# H03.net
KiCad netlist of a schematic drawn in EAGLE
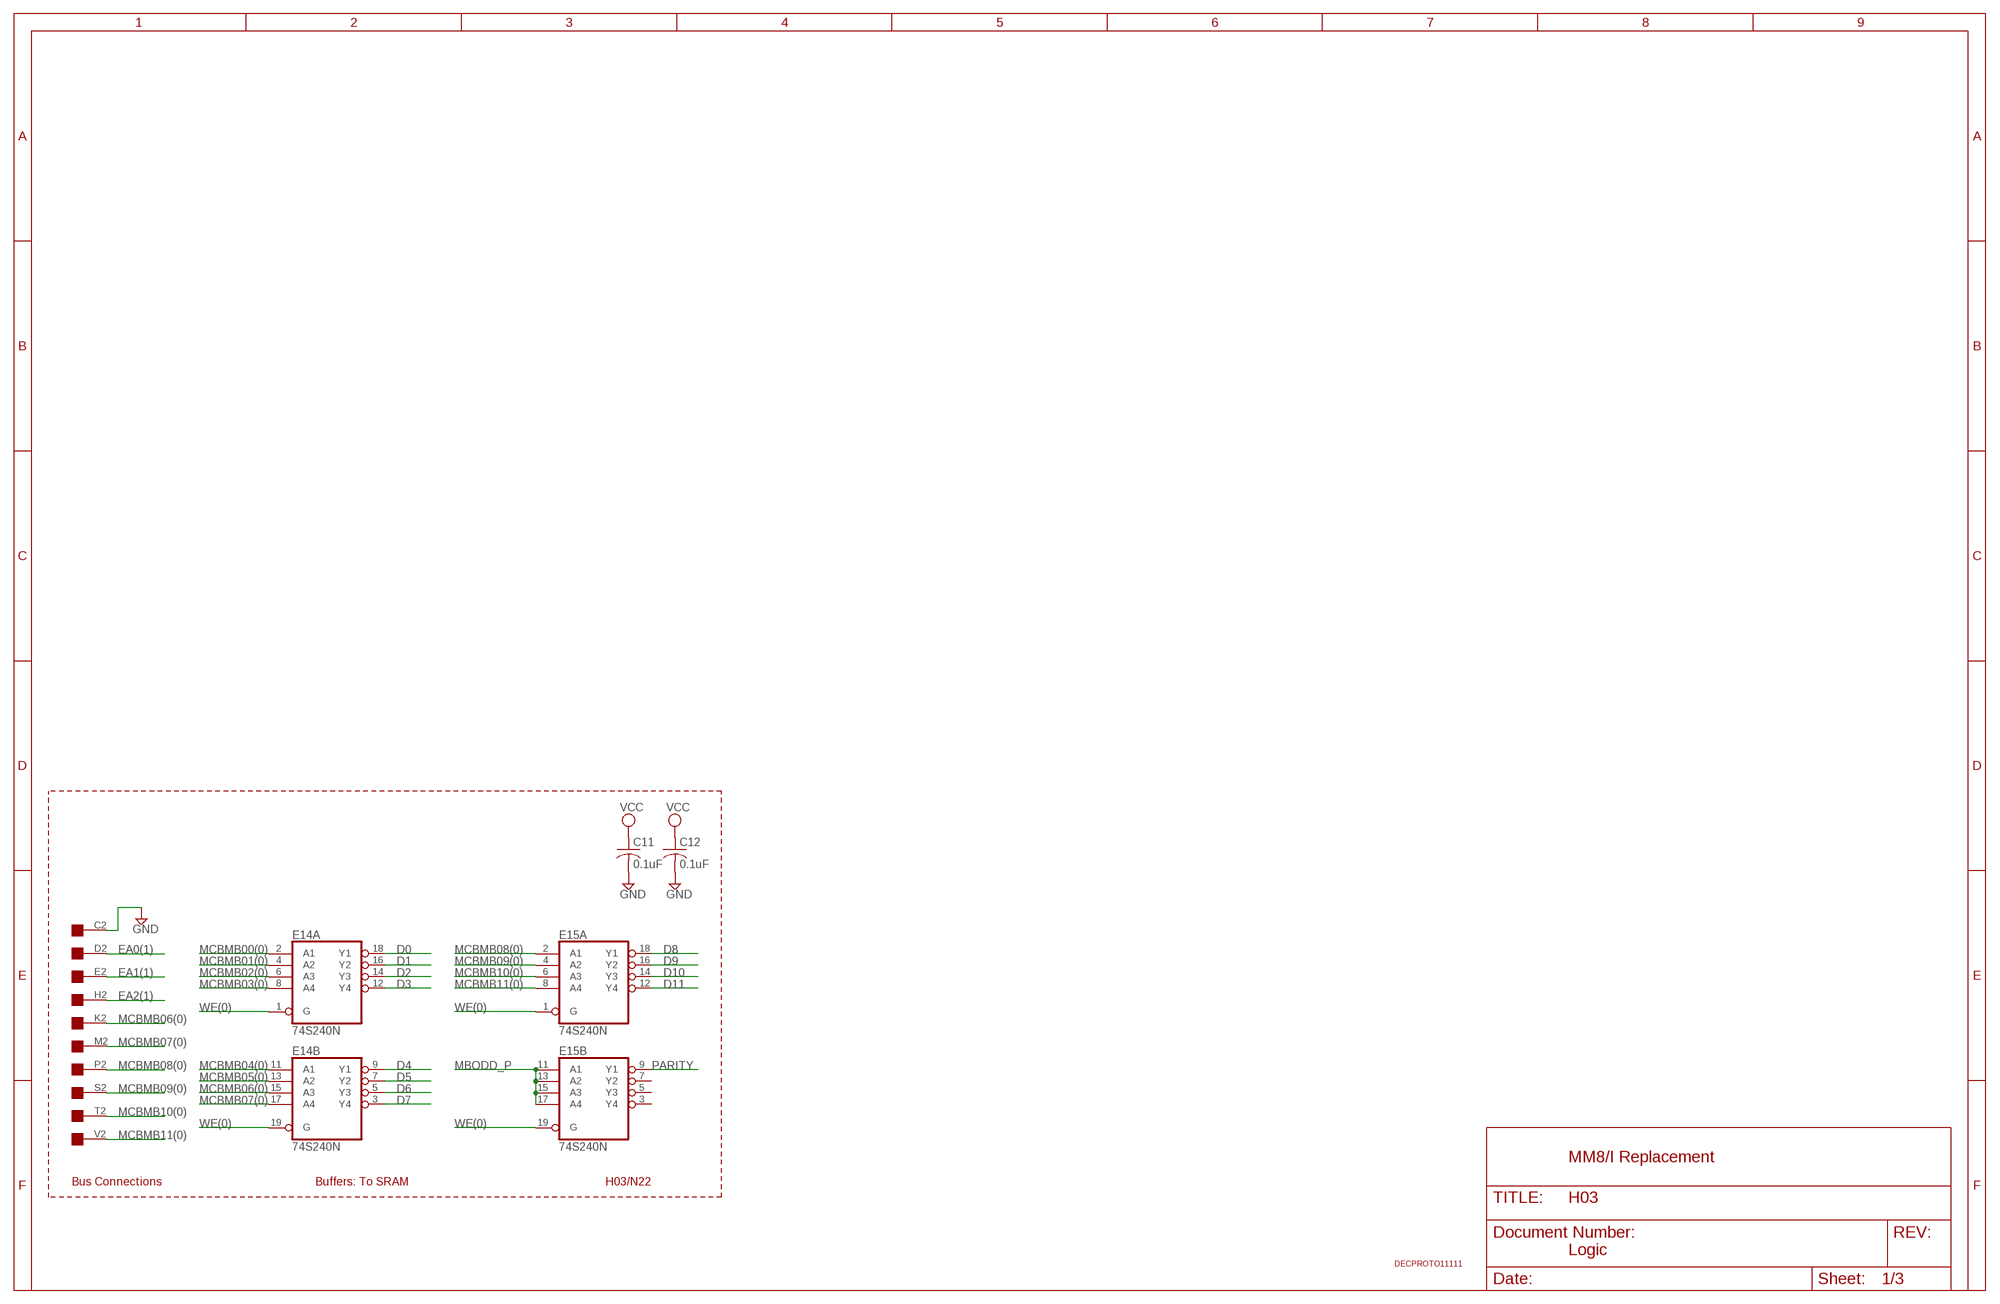
[diagram p0: schematic, sheet 1]
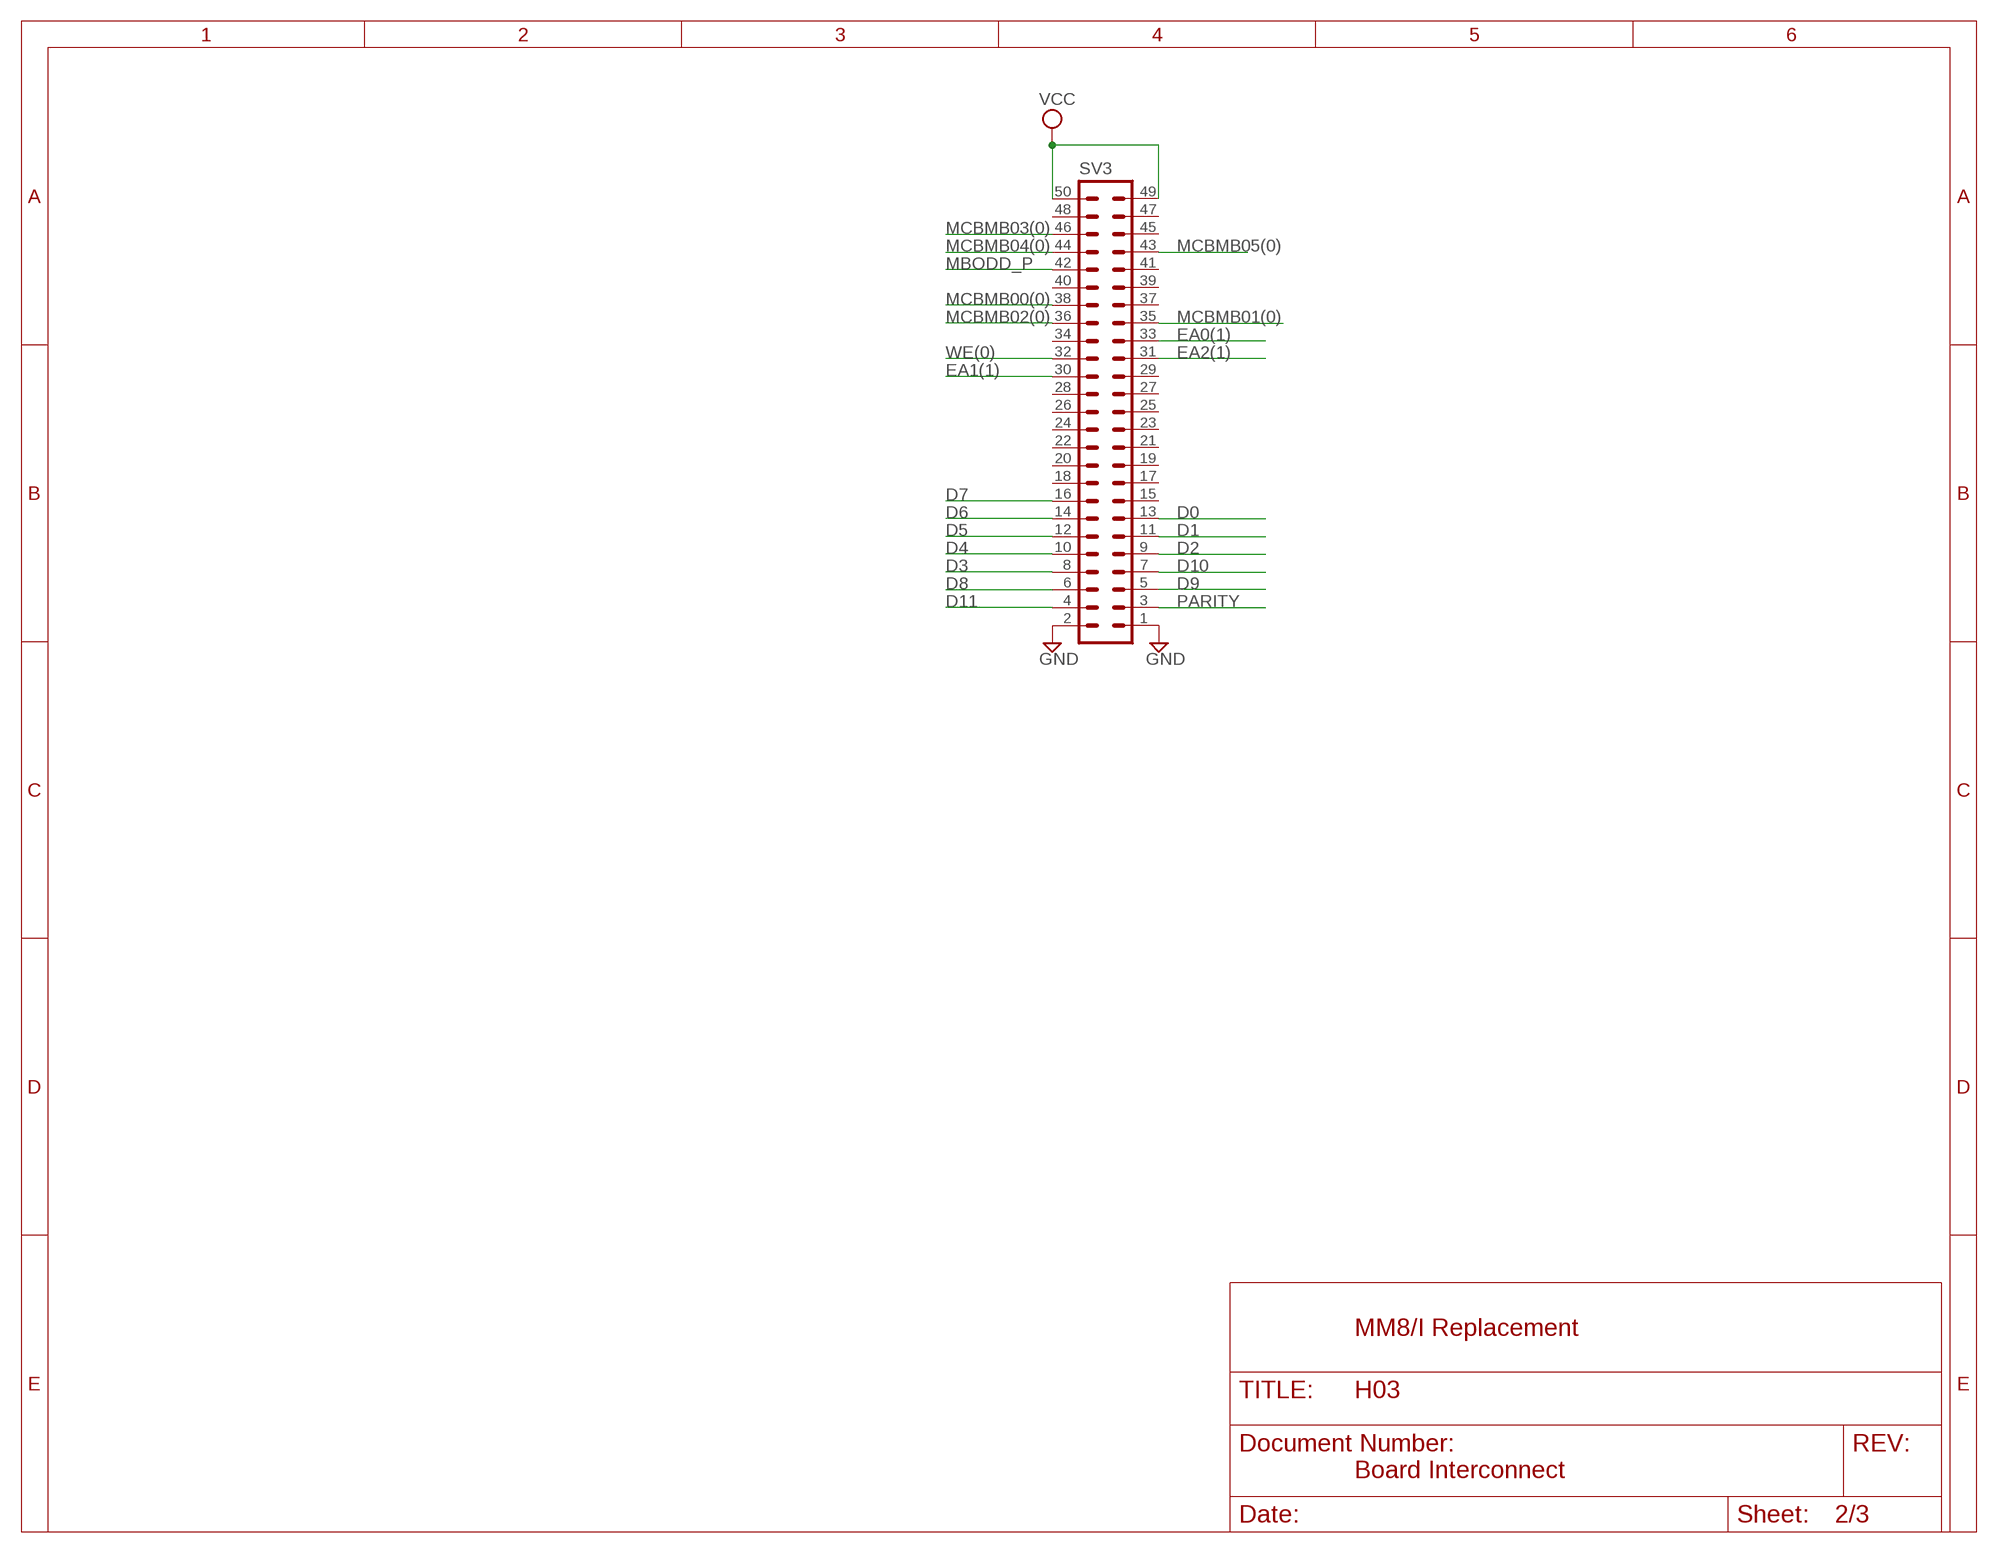
[diagram p1: schematic, sheet 2]
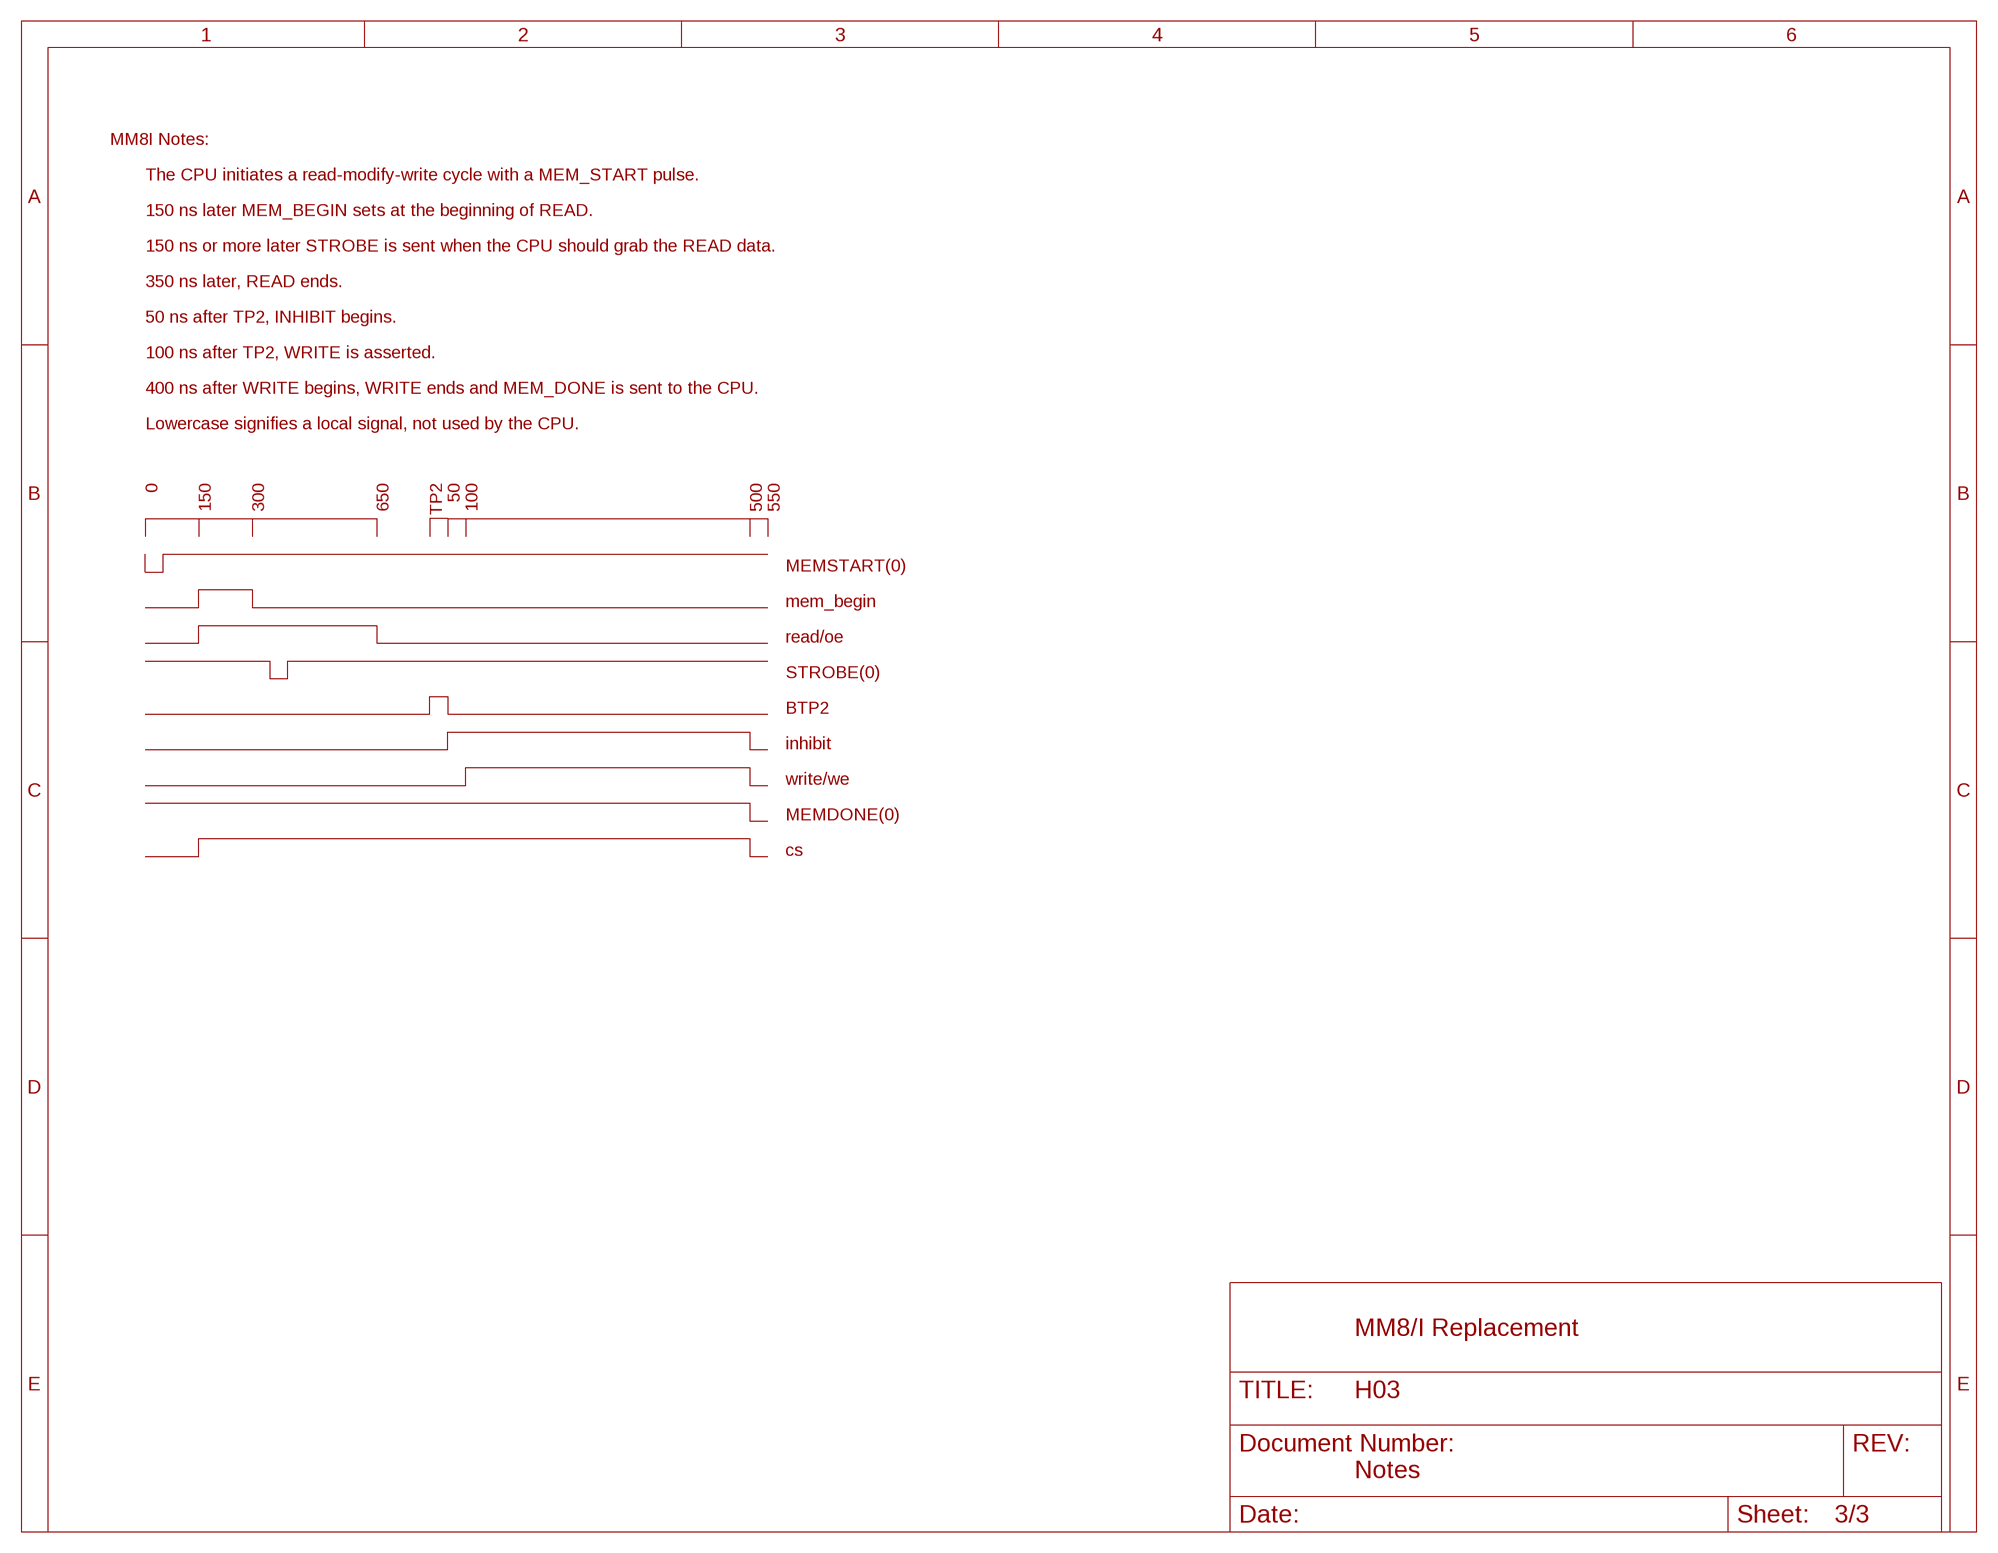
[diagram p2: schematic, sheet 3]

(export (version "E")
  (design (tool "Eeschema 10.0.6"))
  (components
    (comp (ref "C11")
      (value "0.1uF")
      (footprint "eagle-import:C050-025X075")
      (libsource (lib "eagle-import") (part "C-US050-025X075"))
    )
    (comp (ref "C12")
      (value "0.1uF")
      (footprint "eagle-import:C050-025X075")
      (libsource (lib "eagle-import") (part "C-US050-025X075"))
    )
    (comp (ref "E14")
      (value "74S240N")
      (footprint "eagle-import:DIL20")
      (libsource (lib "eagle-import") (part "74240NS"))
    )
    (comp (ref "E15")
      (value "74S240N")
      (footprint "eagle-import:DIL20")
      (libsource (lib "eagle-import") (part "74240NS"))
    )
    (comp (ref "H03")
      (value "EDGE-1")
      (footprint "eagle-import:EDGE-CON1")
      (libsource (lib "eagle-import") (part "EDGE-1"))
    )
    (comp (ref "U$6")
      (value "DECPROTO11111")
      (footprint "eagle-import:DECPROTO11111")
      (libsource (lib "eagle-import") (part "DECPROTO11111"))
    )
    (comp (ref "SV3")
      (value "ML50L")
      (footprint "eagle-import:ML50L")
      (libsource (lib "eagle-import") (part "ML50L"))
    )
  )
  (nets
    (net (code "1") (name "D0") (class "Default")
      (node (ref "E14") (pin "18") (pinfunction "Y1_18") (pintype "tri_state"))
      (node (ref "SV3") (pin "13") (pinfunction "13_13") (pintype "passive"))
    )
    (net (code "2") (name "D1") (class "Default")
      (node (ref "E14") (pin "16") (pinfunction "Y2_16") (pintype "tri_state"))
      (node (ref "SV3") (pin "11") (pinfunction "11_11") (pintype "passive"))
    )
    (net (code "3") (name "D2") (class "Default")
      (node (ref "E14") (pin "14") (pinfunction "Y3_14") (pintype "tri_state"))
      (node (ref "SV3") (pin "9") (pinfunction "9_9") (pintype "passive"))
    )
    (net (code "4") (name "D3") (class "Default")
      (node (ref "E14") (pin "12") (pinfunction "Y4_12") (pintype "tri_state"))
      (node (ref "SV3") (pin "8") (pinfunction "8_8") (pintype "passive"))
    )
    (net (code "5") (name "D4") (class "Default")
      (node (ref "E14") (pin "9") (pinfunction "Y1_9") (pintype "tri_state"))
      (node (ref "SV3") (pin "10") (pinfunction "10_10") (pintype "passive"))
    )
    (net (code "6") (name "D5") (class "Default")
      (node (ref "E14") (pin "7") (pinfunction "Y2_7") (pintype "tri_state"))
      (node (ref "SV3") (pin "12") (pinfunction "12_12") (pintype "passive"))
    )
    (net (code "7") (name "D6") (class "Default")
      (node (ref "E14") (pin "5") (pinfunction "Y3_5") (pintype "tri_state"))
      (node (ref "SV3") (pin "14") (pinfunction "14_14") (pintype "passive"))
    )
    (net (code "8") (name "D7") (class "Default")
      (node (ref "E14") (pin "3") (pinfunction "Y4_3") (pintype "tri_state"))
      (node (ref "SV3") (pin "16") (pinfunction "16_16") (pintype "passive"))
    )
    (net (code "9") (name "D8") (class "Default")
      (node (ref "E15") (pin "18") (pinfunction "Y1_18") (pintype "tri_state"))
      (node (ref "SV3") (pin "6") (pinfunction "6_6") (pintype "passive"))
    )
    (net (code "10") (name "D9") (class "Default")
      (node (ref "E15") (pin "16") (pinfunction "Y2_16") (pintype "tri_state"))
      (node (ref "SV3") (pin "5") (pinfunction "5_5") (pintype "passive"))
    )
    (net (code "11") (name "D10") (class "Default")
      (node (ref "E15") (pin "14") (pinfunction "Y3_14") (pintype "tri_state"))
      (node (ref "SV3") (pin "7") (pinfunction "7_7") (pintype "passive"))
    )
    (net (code "12") (name "D11") (class "Default")
      (node (ref "E15") (pin "12") (pinfunction "Y4_12") (pintype "tri_state"))
      (node (ref "SV3") (pin "4") (pinfunction "4_4") (pintype "passive"))
    )
    (net (code "13") (name "EA0(1)") (class "Default")
      (node (ref "H03") (pin "D2") (pinfunction "1_D2") (pintype "bidirectional"))
      (node (ref "SV3") (pin "33") (pinfunction "33_33") (pintype "passive"))
    )
    (net (code "14") (name "EA1(1)") (class "Default")
      (node (ref "H03") (pin "E2") (pinfunction "1_E2") (pintype "bidirectional"))
      (node (ref "SV3") (pin "30") (pinfunction "30_30") (pintype "passive"))
    )
    (net (code "15") (name "EA2(1)") (class "Default")
      (node (ref "H03") (pin "H2") (pinfunction "1_H2") (pintype "bidirectional"))
      (node (ref "SV3") (pin "31") (pinfunction "31_31") (pintype "passive"))
    )
    (net (code "16") (name "GND") (class "Default")
      (node (ref "C11") (pin "2") (pinfunction "2_2") (pintype "passive"))
      (node (ref "C12") (pin "2") (pinfunction "2_2") (pintype "passive"))
      (node (ref "H03") (pin "C2") (pinfunction "1_C2") (pintype "bidirectional"))
      (node (ref "SV3") (pin "1") (pinfunction "1_1") (pintype "passive"))
      (node (ref "SV3") (pin "2") (pinfunction "2_2") (pintype "passive"))
    )
    (net (code "17") (name "MBODD_P") (class "Default")
      (node (ref "E15") (pin "11") (pinfunction "A1_11") (pintype "input"))
      (node (ref "E15") (pin "13") (pinfunction "A2_13") (pintype "input"))
      (node (ref "E15") (pin "15") (pinfunction "A3_15") (pintype "input"))
      (node (ref "E15") (pin "17") (pinfunction "A4_17") (pintype "input"))
      (node (ref "SV3") (pin "42") (pinfunction "42_42") (pintype "passive"))
    )
    (net (code "18") (name "MCBMB00(0)") (class "Default")
      (node (ref "E14") (pin "2") (pinfunction "A1_2") (pintype "input"))
      (node (ref "SV3") (pin "38") (pinfunction "38_38") (pintype "passive"))
    )
    (net (code "19") (name "MCBMB01(0)") (class "Default")
      (node (ref "E14") (pin "4") (pinfunction "A2_4") (pintype "input"))
      (node (ref "SV3") (pin "35") (pinfunction "35_35") (pintype "passive"))
    )
    (net (code "20") (name "MCBMB02(0)") (class "Default")
      (node (ref "E14") (pin "6") (pinfunction "A3_6") (pintype "input"))
      (node (ref "SV3") (pin "36") (pinfunction "36_36") (pintype "passive"))
    )
    (net (code "21") (name "MCBMB03(0)") (class "Default")
      (node (ref "E14") (pin "8") (pinfunction "A4_8") (pintype "input"))
      (node (ref "SV3") (pin "46") (pinfunction "46_46") (pintype "passive"))
    )
    (net (code "22") (name "MCBMB04(0)") (class "Default")
      (node (ref "E14") (pin "11") (pinfunction "A1_11") (pintype "input"))
      (node (ref "SV3") (pin "44") (pinfunction "44_44") (pintype "passive"))
    )
    (net (code "23") (name "MCBMB05(0)") (class "Default")
      (node (ref "E14") (pin "13") (pinfunction "A2_13") (pintype "input"))
      (node (ref "SV3") (pin "43") (pinfunction "43_43") (pintype "passive"))
    )
    (net (code "24") (name "MCBMB06(0)") (class "Default")
      (node (ref "E14") (pin "15") (pinfunction "A3_15") (pintype "input"))
      (node (ref "H03") (pin "K2") (pinfunction "1_K2") (pintype "bidirectional"))
    )
    (net (code "25") (name "MCBMB07(0)") (class "Default")
      (node (ref "E14") (pin "17") (pinfunction "A4_17") (pintype "input"))
      (node (ref "H03") (pin "M2") (pinfunction "1_M2") (pintype "bidirectional"))
    )
    (net (code "26") (name "MCBMB08(0)") (class "Default")
      (node (ref "E15") (pin "2") (pinfunction "A1_2") (pintype "input"))
      (node (ref "H03") (pin "P2") (pinfunction "1_P2") (pintype "bidirectional"))
    )
    (net (code "27") (name "MCBMB09(0)") (class "Default")
      (node (ref "E15") (pin "4") (pinfunction "A2_4") (pintype "input"))
      (node (ref "H03") (pin "S2") (pinfunction "1_S2") (pintype "bidirectional"))
    )
    (net (code "28") (name "MCBMB10(0)") (class "Default")
      (node (ref "E15") (pin "6") (pinfunction "A3_6") (pintype "input"))
      (node (ref "H03") (pin "T2") (pinfunction "1_T2") (pintype "bidirectional"))
    )
    (net (code "29") (name "MCBMB11(0)") (class "Default")
      (node (ref "E15") (pin "8") (pinfunction "A4_8") (pintype "input"))
      (node (ref "H03") (pin "V2") (pinfunction "1_V2") (pintype "bidirectional"))
    )
    (net (code "30") (name "PARITY") (class "Default")
      (node (ref "E15") (pin "9") (pinfunction "Y1_9") (pintype "tri_state"))
      (node (ref "SV3") (pin "3") (pinfunction "3_3") (pintype "passive"))
    )
    (net (code "31") (name "VCC") (class "Default")
      (node (ref "C11") (pin "1") (pinfunction "1_1") (pintype "passive"))
      (node (ref "C12") (pin "1") (pinfunction "1_1") (pintype "passive"))
      (node (ref "SV3") (pin "49") (pinfunction "49_49") (pintype "passive"))
      (node (ref "SV3") (pin "50") (pinfunction "50_50") (pintype "passive"))
    )
    (net (code "32") (name "WE(0)") (class "Default")
      (node (ref "E14") (pin "1") (pinfunction "G_1") (pintype "input"))
      (node (ref "E14") (pin "19") (pinfunction "G_19") (pintype "input"))
      (node (ref "E15") (pin "1") (pinfunction "G_1") (pintype "input"))
      (node (ref "E15") (pin "19") (pinfunction "G_19") (pintype "input"))
      (node (ref "SV3") (pin "32") (pinfunction "32_32") (pintype "passive"))
    )
    (net (code "33") (name "unconnected-(E15B-Y2-Pad7)") (class "Default")
      (node (ref "E15") (pin "7") (pinfunction "Y2_7") (pintype "tri_state"))
    )
    (net (code "34") (name "unconnected-(E15B-Y3-Pad5)") (class "Default")
      (node (ref "E15") (pin "5") (pinfunction "Y3_5") (pintype "tri_state"))
    )
    (net (code "35") (name "unconnected-(E15B-Y4-Pad3)") (class "Default")
      (node (ref "E15") (pin "3") (pinfunction "Y4_3") (pintype "tri_state"))
    )
    (net (code "36") (name "unconnected-(SV3-Pad15)") (class "Default")
      (node (ref "SV3") (pin "15") (pinfunction "15_15") (pintype "passive"))
    )
    (net (code "37") (name "unconnected-(SV3-Pad17)") (class "Default")
      (node (ref "SV3") (pin "17") (pinfunction "17_17") (pintype "passive"))
    )
    (net (code "38") (name "unconnected-(SV3-Pad18)") (class "Default")
      (node (ref "SV3") (pin "18") (pinfunction "18_18") (pintype "passive"))
    )
    (net (code "39") (name "unconnected-(SV3-Pad19)") (class "Default")
      (node (ref "SV3") (pin "19") (pinfunction "19_19") (pintype "passive"))
    )
    (net (code "40") (name "unconnected-(SV3-Pad20)") (class "Default")
      (node (ref "SV3") (pin "20") (pinfunction "20_20") (pintype "passive"))
    )
    (net (code "41") (name "unconnected-(SV3-Pad21)") (class "Default")
      (node (ref "SV3") (pin "21") (pinfunction "21_21") (pintype "passive"))
    )
    (net (code "42") (name "unconnected-(SV3-Pad22)") (class "Default")
      (node (ref "SV3") (pin "22") (pinfunction "22_22") (pintype "passive"))
    )
    (net (code "43") (name "unconnected-(SV3-Pad23)") (class "Default")
      (node (ref "SV3") (pin "23") (pinfunction "23_23") (pintype "passive"))
    )
    (net (code "44") (name "unconnected-(SV3-Pad24)") (class "Default")
      (node (ref "SV3") (pin "24") (pinfunction "24_24") (pintype "passive"))
    )
    (net (code "45") (name "unconnected-(SV3-Pad25)") (class "Default")
      (node (ref "SV3") (pin "25") (pinfunction "25_25") (pintype "passive"))
    )
    (net (code "46") (name "unconnected-(SV3-Pad26)") (class "Default")
      (node (ref "SV3") (pin "26") (pinfunction "26_26") (pintype "passive"))
    )
    (net (code "47") (name "unconnected-(SV3-Pad27)") (class "Default")
      (node (ref "SV3") (pin "27") (pinfunction "27_27") (pintype "passive"))
    )
    (net (code "48") (name "unconnected-(SV3-Pad28)") (class "Default")
      (node (ref "SV3") (pin "28") (pinfunction "28_28") (pintype "passive"))
    )
    (net (code "49") (name "unconnected-(SV3-Pad29)") (class "Default")
      (node (ref "SV3") (pin "29") (pinfunction "29_29") (pintype "passive"))
    )
    (net (code "50") (name "unconnected-(SV3-Pad34)") (class "Default")
      (node (ref "SV3") (pin "34") (pinfunction "34_34") (pintype "passive"))
    )
    (net (code "51") (name "unconnected-(SV3-Pad37)") (class "Default")
      (node (ref "SV3") (pin "37") (pinfunction "37_37") (pintype "passive"))
    )
    (net (code "52") (name "unconnected-(SV3-Pad39)") (class "Default")
      (node (ref "SV3") (pin "39") (pinfunction "39_39") (pintype "passive"))
    )
    (net (code "53") (name "unconnected-(SV3-Pad40)") (class "Default")
      (node (ref "SV3") (pin "40") (pinfunction "40_40") (pintype "passive"))
    )
    (net (code "54") (name "unconnected-(SV3-Pad41)") (class "Default")
      (node (ref "SV3") (pin "41") (pinfunction "41_41") (pintype "passive"))
    )
    (net (code "55") (name "unconnected-(SV3-Pad45)") (class "Default")
      (node (ref "SV3") (pin "45") (pinfunction "45_45") (pintype "passive"))
    )
    (net (code "56") (name "unconnected-(SV3-Pad47)") (class "Default")
      (node (ref "SV3") (pin "47") (pinfunction "47_47") (pintype "passive"))
    )
    (net (code "57") (name "unconnected-(SV3-Pad48)") (class "Default")
      (node (ref "SV3") (pin "48") (pinfunction "48_48") (pintype "passive"))
    )
  )
)
